# Foot_SMD_V1.net
KiCad netlist of a schematic drawn in EAGLE
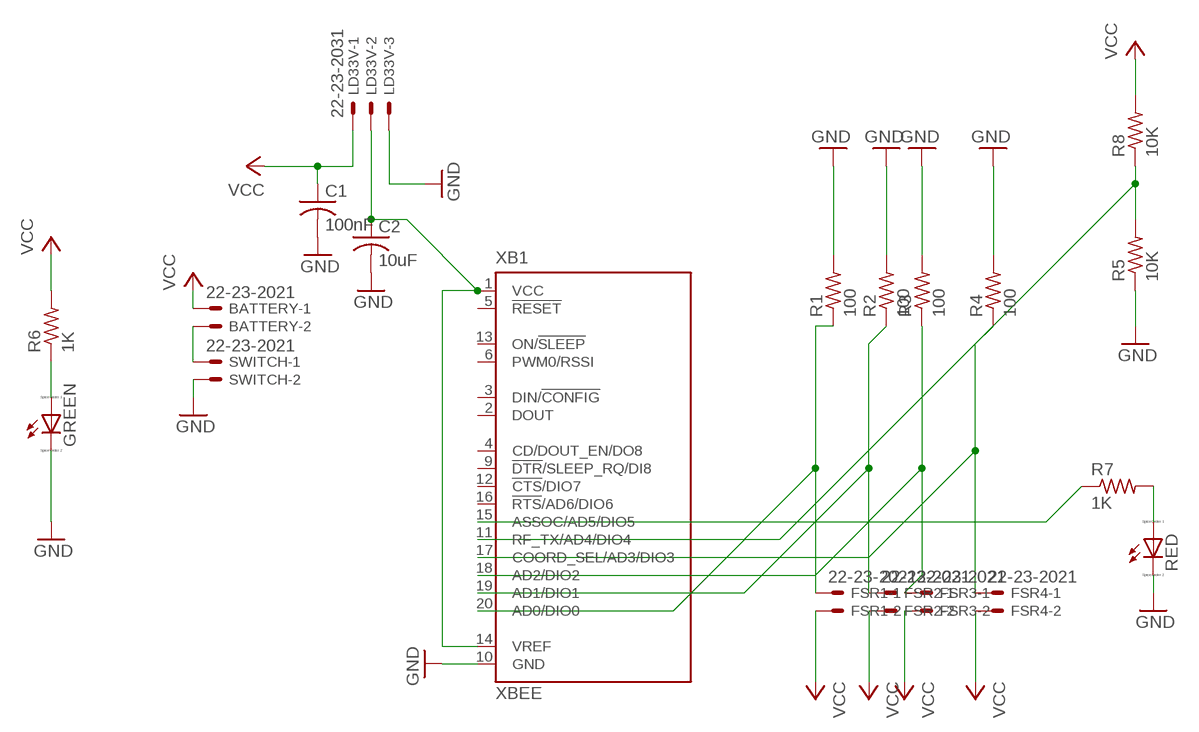
[diagram p0: schematic, sheet 1]

(export (version "E")
  (design (tool "Eeschema 10.0.6"))
  (components
    (comp (ref "BATTERY")
      (value "22-23-2021")
      (footprint "eagle-import:22-23-2021")
      (fields (field (name "MF") "MOLEX"))
      (libsource (lib "eagle-import") (part "22-23-2021"))
    )
    (comp (ref "C1")
      (value "100nF")
      (footprint "eagle-import:C1206")
      (libsource (lib "eagle-import") (part "C-USC1206"))
    )
    (comp (ref "C2")
      (value "10uF")
      (footprint "eagle-import:C1206")
      (libsource (lib "eagle-import") (part "C-USC1206"))
    )
    (comp (ref "FSR1")
      (value "22-23-2021")
      (footprint "eagle-import:22-23-2021")
      (fields (field (name "MF") "MOLEX"))
      (libsource (lib "eagle-import") (part "22-23-2021"))
    )
    (comp (ref "FSR2")
      (value "22-23-2021")
      (footprint "eagle-import:22-23-2021")
      (fields (field (name "MF") "MOLEX"))
      (libsource (lib "eagle-import") (part "22-23-2021"))
    )
    (comp (ref "FSR3")
      (value "22-23-2021")
      (footprint "eagle-import:22-23-2021")
      (fields (field (name "MF") "MOLEX"))
      (libsource (lib "eagle-import") (part "22-23-2021"))
    )
    (comp (ref "FSR4")
      (value "22-23-2021")
      (footprint "eagle-import:22-23-2021")
      (fields (field (name "MF") "MOLEX"))
      (libsource (lib "eagle-import") (part "22-23-2021"))
    )
    (comp (ref "GREEN")
      (value "LED_E")
      (footprint "eagle-import:LED_1206")
      (libsource (lib "eagle-import") (part "LED_E"))
    )
    (comp (ref "LD33V")
      (value "22-23-2031")
      (footprint "eagle-import:22-23-2031")
      (fields (field (name "MF") "MOLEX"))
      (libsource (lib "eagle-import") (part "22-23-2031"))
    )
    (comp (ref "R1")
      (value "100")
      (footprint "eagle-import:M1206")
      (libsource (lib "eagle-import") (part "R-US_M1206"))
    )
    (comp (ref "R2")
      (value "100")
      (footprint "eagle-import:M1206")
      (libsource (lib "eagle-import") (part "R-US_M1206"))
    )
    (comp (ref "R3")
      (value "100")
      (footprint "eagle-import:M1206")
      (libsource (lib "eagle-import") (part "R-US_M1206"))
    )
    (comp (ref "R4")
      (value "100")
      (footprint "eagle-import:M1206")
      (libsource (lib "eagle-import") (part "R-US_M1206"))
    )
    (comp (ref "R5")
      (value "10K")
      (footprint "eagle-import:M1206")
      (libsource (lib "eagle-import") (part "R-US_M1206"))
    )
    (comp (ref "R6")
      (value "1K")
      (footprint "eagle-import:M1206")
      (libsource (lib "eagle-import") (part "R-US_M1206"))
    )
    (comp (ref "R7")
      (value "1K")
      (footprint "eagle-import:M1206")
      (libsource (lib "eagle-import") (part "R-US_M1206"))
    )
    (comp (ref "R8")
      (value "10K")
      (footprint "eagle-import:M1206")
      (libsource (lib "eagle-import") (part "R-US_M1206"))
    )
    (comp (ref "RED")
      (value "LED_E")
      (footprint "eagle-import:LED_1206")
      (libsource (lib "eagle-import") (part "LED_E"))
    )
    (comp (ref "SWITCH")
      (value "22-23-2021")
      (footprint "eagle-import:22-23-2021")
      (fields (field (name "MF") "MOLEX"))
      (libsource (lib "eagle-import") (part "22-23-2021"))
    )
    (comp (ref "XB1")
      (value "XBEE")
      (footprint "eagle-import:XBEE")
      (fields (field (name "MPN") "XBP24-Z7UIT-004"))
      (libsource (lib "eagle-import") (part "XBEE"))
    )
  )
  (nets
    (net (code "1") (name "GND") (class "Default")
      (node (ref "C1") (pin "2") (pinfunction "2_2") (pintype "passive"))
      (node (ref "C2") (pin "2") (pinfunction "2_2") (pintype "passive"))
      (node (ref "GREEN") (pin "C") (pinfunction "C_C") (pintype "passive"))
      (node (ref "LD33V") (pin "3") (pinfunction "S_3") (pintype "passive"))
      (node (ref "R1") (pin "2") (pinfunction "2_2") (pintype "passive"))
      (node (ref "R2") (pin "2") (pinfunction "2_2") (pintype "passive"))
      (node (ref "R3") (pin "2") (pinfunction "2_2") (pintype "passive"))
      (node (ref "R4") (pin "2") (pinfunction "2_2") (pintype "passive"))
      (node (ref "R5") (pin "1") (pinfunction "1_1") (pintype "passive"))
      (node (ref "RED") (pin "C") (pinfunction "C_C") (pintype "passive"))
      (node (ref "SWITCH") (pin "2") (pinfunction "S_2") (pintype "passive"))
      (node (ref "XB1") (pin "10") (pinfunction "GND_10") (pintype "power_in"))
    )
    (net (code "2") (name "Net-(BATTERYB-S)") (class "Default")
      (node (ref "BATTERY") (pin "2") (pinfunction "S_2") (pintype "passive"))
      (node (ref "SWITCH") (pin "1") (pinfunction "S_1") (pintype "passive"))
    )
    (net (code "3") (name "Net-(FSR1A-S)") (class "Default")
      (node (ref "FSR1") (pin "1") (pinfunction "S_1") (pintype "passive"))
      (node (ref "R1") (pin "1") (pinfunction "1_1") (pintype "passive"))
      (node (ref "XB1") (pin "20") (pinfunction "AD0/DIO0_20") (pintype "bidirectional"))
    )
    (net (code "4") (name "Net-(FSR2A-S)") (class "Default")
      (node (ref "FSR2") (pin "1") (pinfunction "S_1") (pintype "passive"))
      (node (ref "R2") (pin "1") (pinfunction "1_1") (pintype "passive"))
      (node (ref "XB1") (pin "19") (pinfunction "AD1/DIO1_19") (pintype "bidirectional"))
    )
    (net (code "5") (name "Net-(FSR3A-S)") (class "Default")
      (node (ref "FSR3") (pin "1") (pinfunction "S_1") (pintype "passive"))
      (node (ref "R3") (pin "1") (pinfunction "1_1") (pintype "passive"))
      (node (ref "XB1") (pin "18") (pinfunction "AD2/DIO2_18") (pintype "bidirectional"))
    )
    (net (code "6") (name "Net-(FSR4A-S)") (class "Default")
      (node (ref "FSR4") (pin "1") (pinfunction "S_1") (pintype "passive"))
      (node (ref "R4") (pin "1") (pinfunction "1_1") (pintype "passive"))
      (node (ref "XB1") (pin "17") (pinfunction "COORD_SEL/AD3/DIO3_17") (pintype "bidirectional"))
    )
    (net (code "7") (name "Net-(GREEN-PadA)") (class "Default")
      (node (ref "GREEN") (pin "A") (pinfunction "A_A") (pintype "passive"))
      (node (ref "R6") (pin "1") (pinfunction "1_1") (pintype "passive"))
    )
    (net (code "8") (name "Net-(LD33VB-S)") (class "Default")
      (node (ref "C2") (pin "1") (pinfunction "1_1") (pintype "passive"))
      (node (ref "LD33V") (pin "2") (pinfunction "S_2") (pintype "passive"))
      (node (ref "XB1") (pin "1") (pinfunction "VCC_1") (pintype "power_in"))
      (node (ref "XB1") (pin "14") (pinfunction "VREF_14") (pintype "input"))
    )
    (net (code "9") (name "Net-(R7-Pad2)") (class "Default")
      (node (ref "R7") (pin "2") (pinfunction "2_2") (pintype "passive"))
      (node (ref "RED") (pin "A") (pinfunction "A_A") (pintype "passive"))
    )
    (net (code "10") (name "Net-(XB1-ASSOC{slash}AD5{slash}DIO5)") (class "Default")
      (node (ref "R7") (pin "1") (pinfunction "1_1") (pintype "passive"))
      (node (ref "XB1") (pin "15") (pinfunction "ASSOC/AD5/DIO5_15") (pintype "bidirectional"))
    )
    (net (code "11") (name "Net-(XB1-RF_TX{slash}AD4{slash}DIO4)") (class "Default")
      (node (ref "R5") (pin "2") (pinfunction "2_2") (pintype "passive"))
      (node (ref "R8") (pin "1") (pinfunction "1_1") (pintype "passive"))
      (node (ref "XB1") (pin "11") (pinfunction "RF_TX/AD4/DIO4_11") (pintype "bidirectional"))
    )
    (net (code "12") (name "VCC") (class "Default")
      (node (ref "BATTERY") (pin "1") (pinfunction "S_1") (pintype "passive"))
      (node (ref "C1") (pin "1") (pinfunction "1_1") (pintype "passive"))
      (node (ref "FSR1") (pin "2") (pinfunction "S_2") (pintype "passive"))
      (node (ref "FSR2") (pin "2") (pinfunction "S_2") (pintype "passive"))
      (node (ref "FSR3") (pin "2") (pinfunction "S_2") (pintype "passive"))
      (node (ref "FSR4") (pin "2") (pinfunction "S_2") (pintype "passive"))
      (node (ref "LD33V") (pin "1") (pinfunction "S_1") (pintype "passive"))
      (node (ref "R6") (pin "2") (pinfunction "2_2") (pintype "passive"))
      (node (ref "R8") (pin "2") (pinfunction "2_2") (pintype "passive"))
    )
    (net (code "13") (name "unconnected-(XB1-CD{slash}DOUT_EN{slash}DO8-Pad4)") (class "Default")
      (node (ref "XB1") (pin "4") (pinfunction "CD/DOUT_EN/DO8_4") (pintype "output"))
    )
    (net (code "14") (name "unconnected-(XB1-DIN{slash}~{CONFIG}-Pad3)") (class "Default")
      (node (ref "XB1") (pin "3") (pinfunction "DIN/~{CONFIG}_3") (pintype "input"))
    )
    (net (code "15") (name "unconnected-(XB1-DOUT-Pad2)") (class "Default")
      (node (ref "XB1") (pin "2") (pinfunction "DOUT_2") (pintype "output"))
    )
    (net (code "16") (name "unconnected-(XB1-ON{slash}~{SLEEP}-Pad13)") (class "Default")
      (node (ref "XB1") (pin "13") (pinfunction "ON/~{SLEEP}_13") (pintype "output"))
    )
    (net (code "17") (name "unconnected-(XB1-PWM0{slash}RSSI-Pad6)") (class "Default")
      (node (ref "XB1") (pin "6") (pinfunction "PWM0/RSSI_6") (pintype "output"))
    )
    (net (code "18") (name "unconnected-(XB1-~{CTS}{slash}DIO7-Pad12)") (class "Default")
      (node (ref "XB1") (pin "12") (pinfunction "~{CTS}/DIO7_12") (pintype "bidirectional"))
    )
    (net (code "19") (name "unconnected-(XB1-~{DTR}{slash}SLEEP_RQ{slash}DI8-Pad9)") (class "Default")
      (node (ref "XB1") (pin "9") (pinfunction "~{DTR}/SLEEP_RQ/DI8_9") (pintype "bidirectional"))
    )
    (net (code "20") (name "unconnected-(XB1-~{RESET}-Pad5)") (class "Default")
      (node (ref "XB1") (pin "5") (pinfunction "~{RESET}_5") (pintype "input"))
    )
    (net (code "21") (name "unconnected-(XB1-~{RTS}{slash}AD6{slash}DIO6-Pad16)") (class "Default")
      (node (ref "XB1") (pin "16") (pinfunction "~{RTS}/AD6/DIO6_16") (pintype "bidirectional"))
    )
  )
)
